# BoschPumpDriver.net
KiCad netlist of a schematic drawn in EAGLE
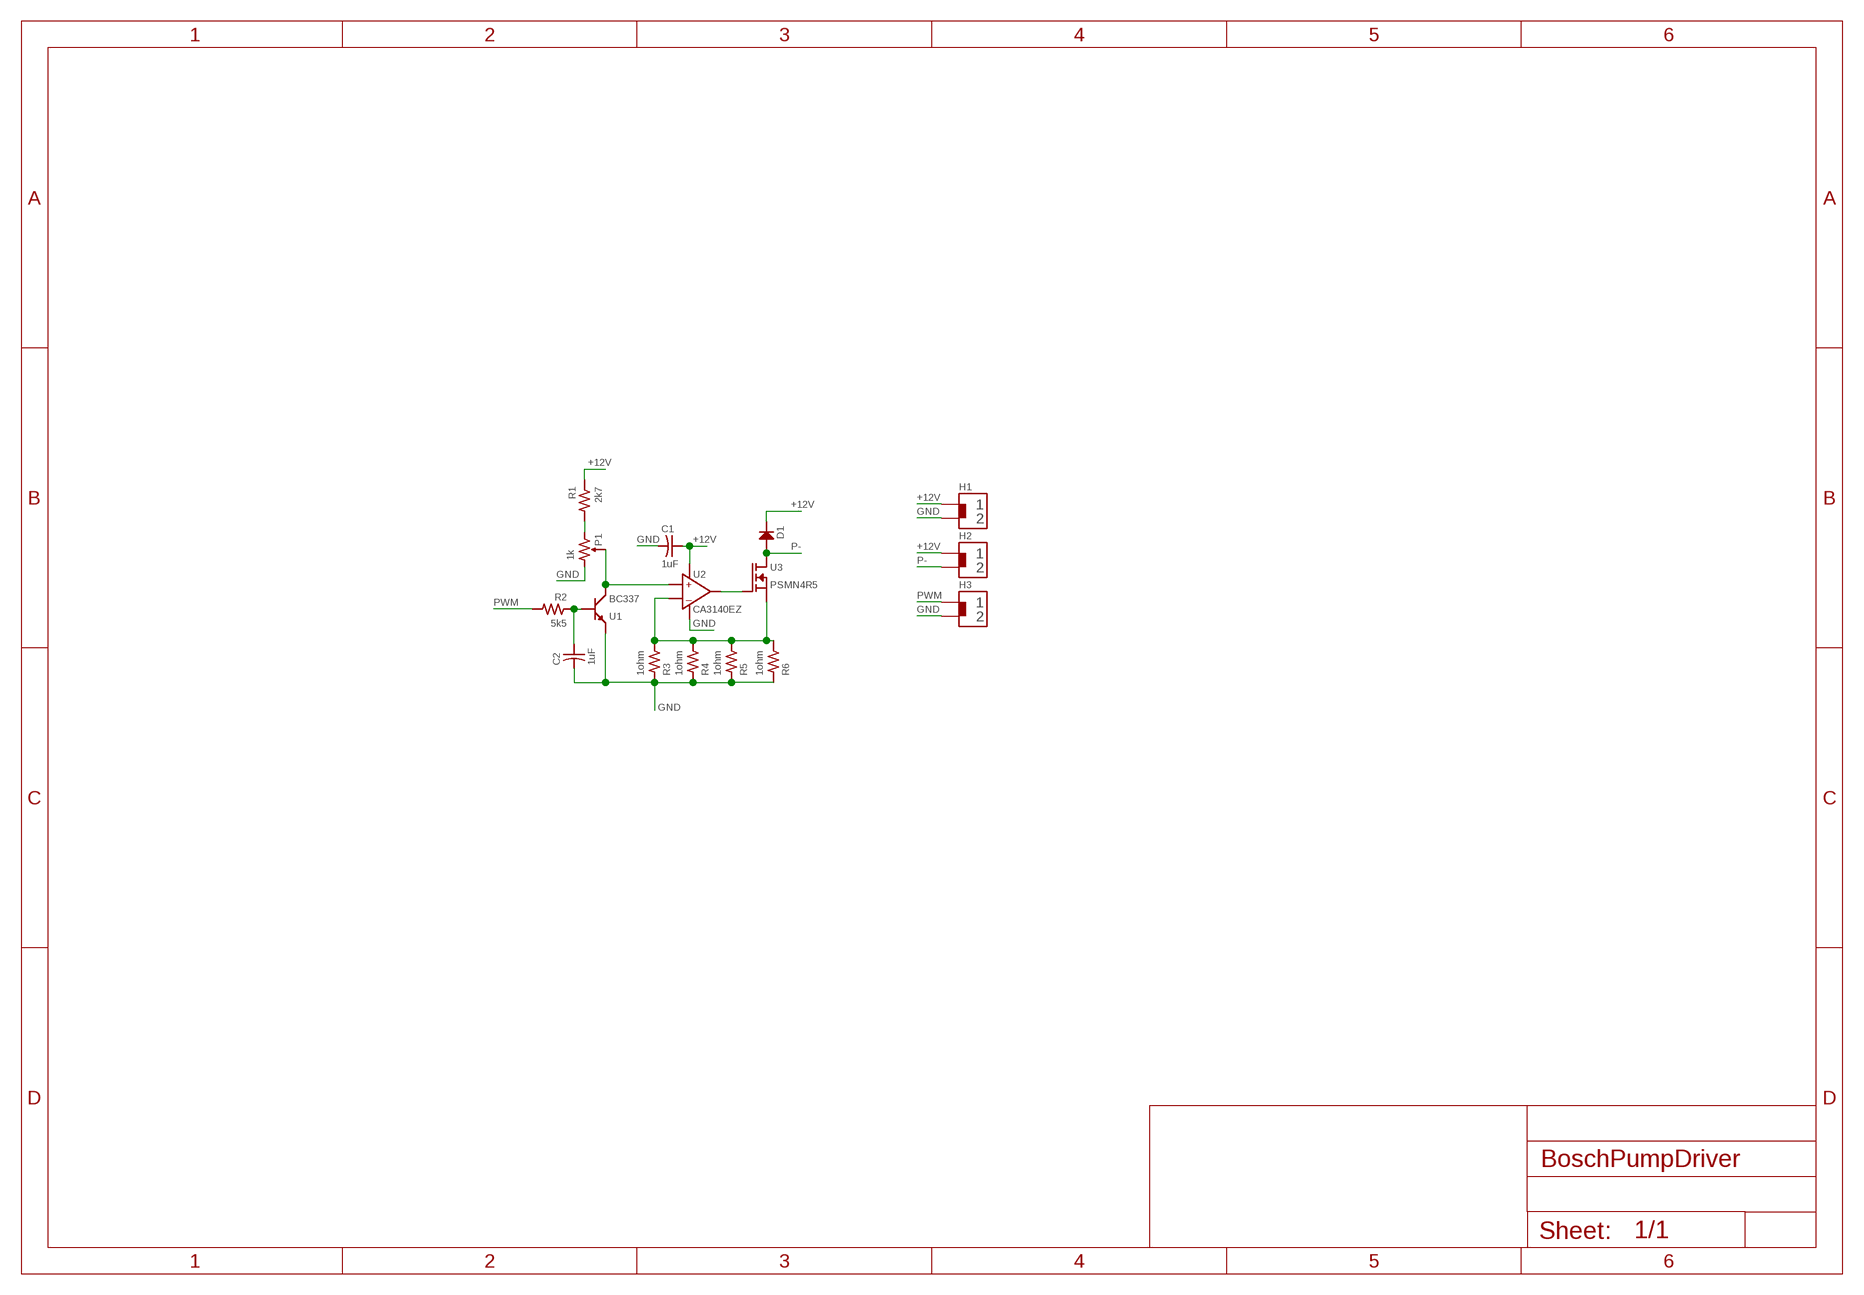
[diagram p0: schematic, sheet 1]

(export (version "E")
  (design (tool "Eeschema 10.0.6"))
  (components
    (comp (ref "C1")
      (value "1uF")
      (footprint "eagle-import:CRS100NF")
      (libsource (lib "eagle-import") (part "CTH"))
    )
    (comp (ref "C2")
      (value "1uF")
      (footprint "eagle-import:CRS100NF")
      (libsource (lib "eagle-import") (part "CTH"))
    )
    (comp (ref "D1")
      (value "DIODEVERT")
      (footprint "eagle-import:R_VERT")
      (libsource (lib "eagle-import") (part "DIODEVERT"))
    )
    (comp (ref "H1")
      (value "VCC")
      (footprint "eagle-import:HEADER2PIN")
      (libsource (lib "eagle-import") (part "HEADER2PINPAD_ROUND"))
    )
    (comp (ref "H2")
      (value "PUMP")
      (footprint "eagle-import:HEADER2PIN")
      (libsource (lib "eagle-import") (part "HEADER2PINPAD_ROUND"))
    )
    (comp (ref "H3")
      (value "PWM")
      (footprint "eagle-import:HEADER2PIN")
      (libsource (lib "eagle-import") (part "HEADER2PINPAD_ROUND"))
    )
    (comp (ref "P1")
      (value "1k")
      (footprint "eagle-import:3PIN_POT_2.54")
      (libsource (lib "eagle-import") (part "POTENTIOMETER2.54_3PIN"))
    )
    (comp (ref "R1")
      (value "2k7")
      (footprint "eagle-import:R1_4TH")
      (libsource (lib "eagle-import") (part "RORR"))
    )
    (comp (ref "R2")
      (value "5k5")
      (footprint "eagle-import:R_VERT")
      (libsource (lib "eagle-import") (part "RVERT"))
    )
    (comp (ref "R3")
      (value "1ohm")
      (footprint "eagle-import:R_VERT")
      (libsource (lib "eagle-import") (part "RVERT"))
    )
    (comp (ref "R4")
      (value "1ohm")
      (footprint "eagle-import:R_VERT")
      (libsource (lib "eagle-import") (part "RVERT"))
    )
    (comp (ref "R5")
      (value "1ohm")
      (footprint "eagle-import:R_VERT")
      (libsource (lib "eagle-import") (part "RVERT"))
    )
    (comp (ref "R6")
      (value "1ohm")
      (footprint "eagle-import:R_VERT")
      (libsource (lib "eagle-import") (part "RVERT"))
    )
    (comp (ref "U1")
      (value "BC337")
      (footprint "eagle-import:TO92")
      (libsource (lib "eagle-import") (part "BJT_NPNBC337"))
    )
    (comp (ref "U2")
      (value "CA3140EZ")
      (footprint "eagle-import:DIP8")
      (libsource (lib "eagle-import") (part "OPAMP_1CA3140EZ_PDIP8"))
    )
    (comp (ref "U3")
      (value "PSMN4R5")
      (footprint "eagle-import:TO-220")
      (libsource (lib "eagle-import") (part "MOSFET_NPSMN4R5"))
    )
  )
  (nets
    (net (code "1") (name "/+12V") (class "Default")
      (node (ref "C1") (pin "+") (pinfunction "+_+") (pintype "bidirectional"))
      (node (ref "D1") (pin "2") (pinfunction "OUT_2") (pintype "bidirectional"))
      (node (ref "H1") (pin "1") (pinfunction "1_1") (pintype "bidirectional"))
      (node (ref "H2") (pin "1") (pinfunction "1_1") (pintype "bidirectional"))
      (node (ref "R1") (pin "P$1") (pinfunction "P$1_P$1") (pintype "bidirectional"))
      (node (ref "U2") (pin "7") (pinfunction "VCC+_7") (pintype "bidirectional"))
    )
    (net (code "2") (name "/GND") (class "Default")
      (node (ref "C1") (pin "-") (pinfunction "-_-") (pintype "bidirectional"))
      (node (ref "C2") (pin "-") (pinfunction "-_-") (pintype "bidirectional"))
      (node (ref "H1") (pin "2") (pinfunction "2_2") (pintype "bidirectional"))
      (node (ref "H3") (pin "2") (pinfunction "2_2") (pintype "bidirectional"))
      (node (ref "P1") (pin "1") (pinfunction "1_1") (pintype "bidirectional"))
      (node (ref "R3") (pin "1") (pinfunction "P$1_1") (pintype "bidirectional"))
      (node (ref "R4") (pin "1") (pinfunction "P$1_1") (pintype "bidirectional"))
      (node (ref "R5") (pin "1") (pinfunction "P$1_1") (pintype "bidirectional"))
      (node (ref "R6") (pin "1") (pinfunction "P$1_1") (pintype "bidirectional"))
      (node (ref "U1") (pin "3") (pinfunction "E_3") (pintype "bidirectional"))
      (node (ref "U2") (pin "4") (pinfunction "VCC-_4") (pintype "bidirectional"))
    )
    (net (code "3") (name "/P-") (class "Default")
      (node (ref "D1") (pin "1") (pinfunction "IN_1") (pintype "bidirectional"))
      (node (ref "H2") (pin "2") (pinfunction "2_2") (pintype "bidirectional"))
      (node (ref "U3") (pin "2") (pinfunction "D_2") (pintype "bidirectional"))
    )
    (net (code "4") (name "/PWM") (class "Default")
      (node (ref "H3") (pin "1") (pinfunction "1_1") (pintype "bidirectional"))
      (node (ref "R2") (pin "2") (pinfunction "P$2_2") (pintype "bidirectional"))
    )
    (net (code "5") (name "Net-(P1-Pad3)") (class "Default")
      (node (ref "P1") (pin "3") (pinfunction "3_3") (pintype "bidirectional"))
      (node (ref "R1") (pin "P$2") (pinfunction "P$2_P$2") (pintype "bidirectional"))
    )
    (net (code "6") (name "Net-(R2-P$1)") (class "Default")
      (node (ref "C2") (pin "+") (pinfunction "+_+") (pintype "bidirectional"))
      (node (ref "R2") (pin "1") (pinfunction "P$1_1") (pintype "bidirectional"))
      (node (ref "U1") (pin "2") (pinfunction "B_2") (pintype "bidirectional"))
    )
    (net (code "7") (name "Net-(R3-P$2)") (class "Default")
      (node (ref "R3") (pin "2") (pinfunction "P$2_2") (pintype "bidirectional"))
      (node (ref "R4") (pin "2") (pinfunction "P$2_2") (pintype "bidirectional"))
      (node (ref "R5") (pin "2") (pinfunction "P$2_2") (pintype "bidirectional"))
      (node (ref "R6") (pin "2") (pinfunction "P$2_2") (pintype "bidirectional"))
      (node (ref "U2") (pin "2") (pinfunction "IN-_2") (pintype "bidirectional"))
      (node (ref "U3") (pin "3") (pinfunction "S_3") (pintype "bidirectional"))
    )
    (net (code "8") (name "Net-(U1-C)") (class "Default")
      (node (ref "P1") (pin "2") (pinfunction "2_2") (pintype "bidirectional"))
      (node (ref "U1") (pin "1") (pinfunction "C_1") (pintype "bidirectional"))
      (node (ref "U2") (pin "3") (pinfunction "IN+_3") (pintype "bidirectional"))
    )
    (net (code "9") (name "Net-(U2-OUT)") (class "Default")
      (node (ref "U2") (pin "6") (pinfunction "OUT_6") (pintype "bidirectional"))
      (node (ref "U3") (pin "1") (pinfunction "G_1") (pintype "bidirectional"))
    )
  )
)
